# PSU.net
KiCad netlist of a schematic drawn in Altium Designer
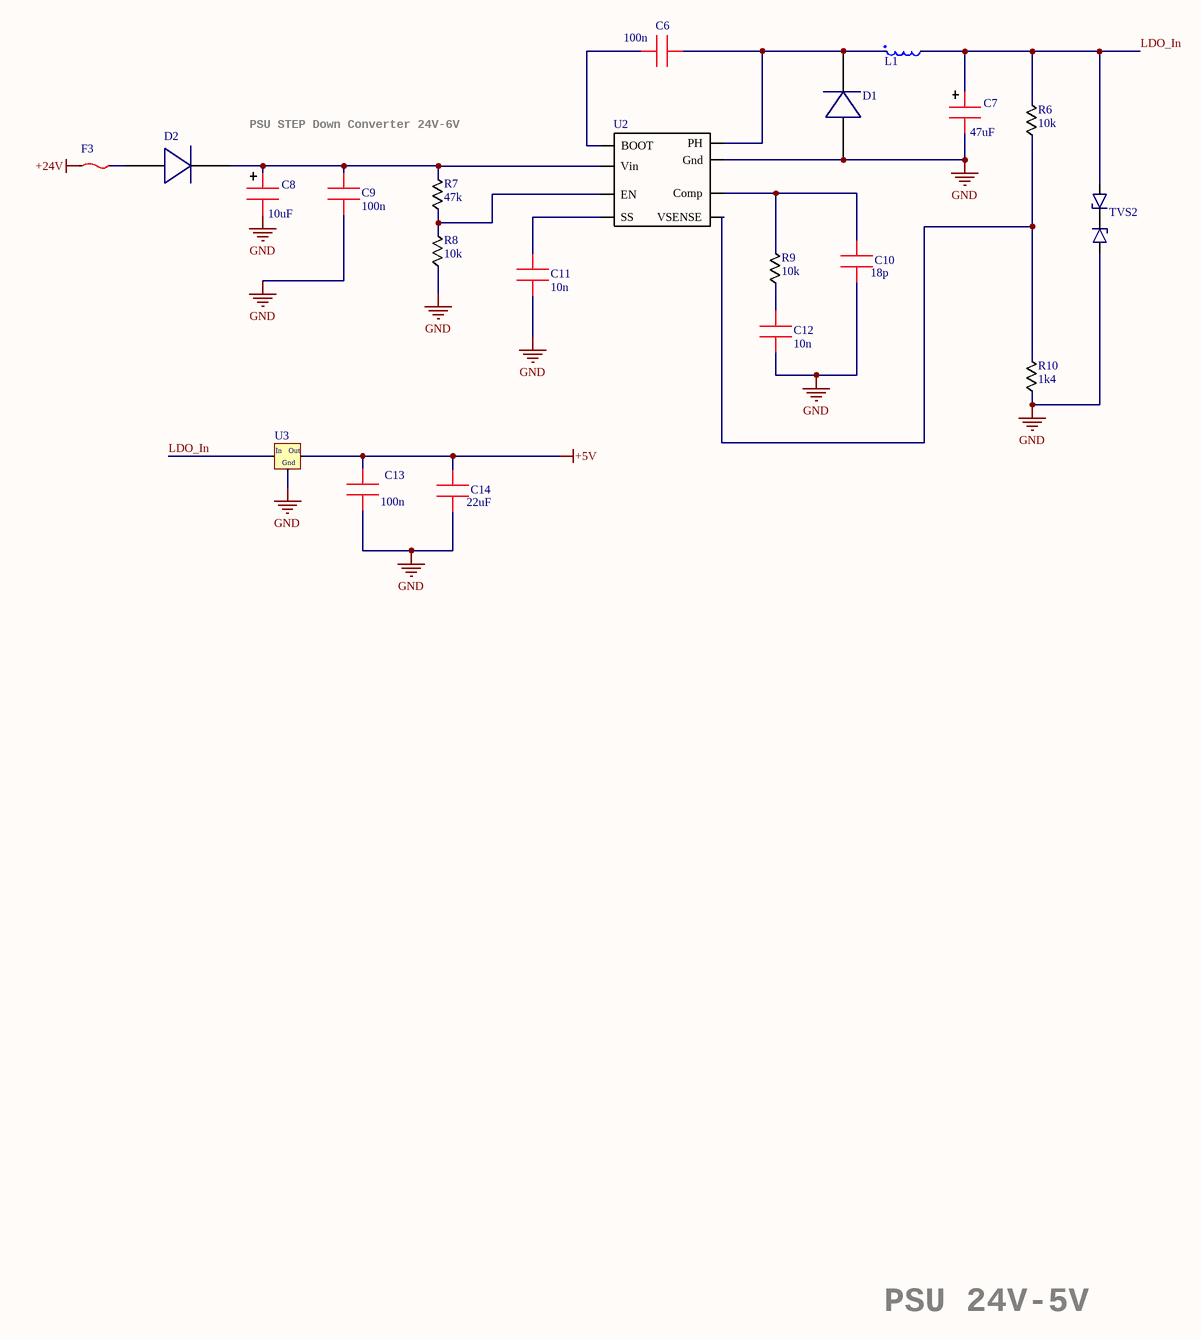
[diagram p0: PSU.SchDoc]

(export (version "E")
  (design (tool "Eeschema 10.0.6"))
  (components
    (comp (ref "C6")
      (value "100n")
      (footprint "0603 - Cap")
      (fields (field (name "PART NUMBER") "CC0603KRX7R9BB104"))
      (libsource (lib "kontr") (part "0805 Cap"))
    )
    (comp (ref "C7")
      (value "47uF")
      (footprint "1210")
      (fields (field (name "PART NUMBER") "GRM32ER71A476KE15L"))
      (libsource (lib "") (part "1206 Cap El_1"))
    )
    (comp (ref "C8")
      (value "10uF")
      (footprint "1210")
      (fields (field (name "PART NUMBER") "GRM32ER71H106KA12L"))
      (libsource (lib "kontr") (part "1206 Cap El"))
    )
    (comp (ref "C9")
      (value "100n")
      (footprint "0603 - Cap")
      (fields (field (name "PART NUMBER") "CC0603KRX7R9BB104"))
      (libsource (lib "kontr") (part "0805 Cap"))
    )
    (comp (ref "C10")
      (value "18p")
      (footprint "0603 - Cap")
      (fields (field (name "PART NUMBER") "CC0603JRNPO9BN180"))
      (libsource (lib "kontr") (part "0805 Cap"))
    )
    (comp (ref "C11")
      (value "10n")
      (footprint "0603 - Cap")
      (fields (field (name "PART NUMBER") "GRM1885C1H103JA01D"))
      (libsource (lib "kontr") (part "0805 Cap"))
    )
    (comp (ref "C12")
      (value "10n")
      (footprint "0603 - Cap")
      (fields (field (name "PART NUMBER") "GRM1885C1H103JA01D"))
      (libsource (lib "kontr") (part "0805 Cap"))
    )
    (comp (ref "C13")
      (value "100n")
      (footprint "0603 - Cap")
      (description "CC0603ZRY5V9BB104")
      (fields (field (name "PART NUMBER") "CC0603KRX7R9BB104"))
      (libsource (lib "kontr") (part "Capasitor 0805"))
    )
    (comp (ref "C14")
      (value "22uF")
      (footprint "1206")
      (fields (field (name "PART NUMBER") "CC1210KKX5R7BB226"))
      (libsource (lib "kontr") (part "0805 Cap"))
    )
    (comp (ref "D1")
      (value "~")
      (footprint "B340A-13-F")
      (fields (field (name "PART NUMBER") "B360A-13-F"))
      (libsource (lib "kontr") (part "B340A-13-F"))
    )
    (comp (ref "D2")
      (value "~")
      (footprint "B340A-13-F")
      (fields (field (name "PART NUMBER") "B360A-13-F"))
      (libsource (lib "kontr") (part "B340A-13-F"))
    )
    (comp (ref "F3")
      (value "~")
      (footprint "MSMF")
      (fields (field (name "PART NUMBER") "MF-MSMF010-2"))
      (libsource (lib "kontr") (part "MSMF"))
    )
    (comp (ref "L1")
      (value "~")
      (footprint "SRU1048")
      (fields (field (name "PART NUMBER") "SRU1048-330Y"))
      (libsource (lib "kontr") (part "CDRH127"))
    )
    (comp (ref "R6")
      (value "10k")
      (footprint "0603_Res")
      (fields (field (name "PART NUMBER") "RC0603FR-0710KL"))
      (libsource (lib "kontr") (part "Resistor 0805"))
    )
    (comp (ref "R7")
      (value "47k")
      (footprint "0603_Res")
      (description "RC0603JR-0747K")
      (libsource (lib "kontr") (part "Resistor 0805"))
    )
    (comp (ref "R8")
      (value "10k")
      (footprint "0603_Res")
      (fields (field (name "PART NUMBER") "RC0603FR-0710KL"))
      (libsource (lib "kontr") (part "Resistor 0805"))
    )
    (comp (ref "R9")
      (value "10k")
      (footprint "0603_Res")
      (fields (field (name "PART NUMBER") "RC0603FR-0710KL"))
      (libsource (lib "kontr") (part "Resistor 0805"))
    )
    (comp (ref "R10")
      (value "1k4")
      (footprint "0603_Res")
      (fields (field (name "PART NUMBER") "RC0603FR-071K4L"))
      (libsource (lib "kontr") (part "Resistor 0805"))
    )
    (comp (ref "TVS2")
      (value "~")
      (footprint "SM6T")
      (fields (field (name "PART NUMBER") "SM6T12CA"))
      (libsource (lib "kontr") (part "SM6T"))
    )
    (comp (ref "U2")
      (value "~")
      (footprint "SOIC 8")
      (fields (field (name "PART NUMBER") "TPS54331"))
      (libsource (lib "kontr") (part "TPS54331"))
    )
    (comp (ref "U3")
      (value "~")
      (footprint "SOT223")
      (fields (field (name "PART NUMBER") "LM1117MPX-5.0"))
      (libsource (lib "kontr") (part "NCV1117ST50T3G"))
    )
  )
  (nets
    (net (code "1") (name "+5V") (class "Default")
      (node (ref "C13") (pin "1") (pinfunction "1_1") (pintype "passive"))
      (node (ref "C14") (pin "2") (pinfunction "2_2") (pintype "passive"))
      (node (ref "U3") (pin "2") (pinfunction "OUT_2") (pintype "passive"))
    )
    (net (code "2") (name "+24V") (class "Default")
      (node (ref "F3") (pin "0") (pinfunction "0_0") (pintype "passive"))
    )
    (net (code "3") (name "/LDO_In") (class "Default")
      (node (ref "C7") (pin "1") (pinfunction "1_1") (pintype "passive"))
      (node (ref "L1") (pin "2") (pinfunction "2_2") (pintype "passive"))
      (node (ref "R6") (pin "2") (pintype "passive"))
      (node (ref "TVS2") (pin "2") (pinfunction "2_2") (pintype "passive"))
      (node (ref "U3") (pin "3") (pinfunction "IN_3") (pintype "passive"))
    )
    (net (code "4") (name "GND") (class "Default")
      (node (ref "C10") (pin "1") (pinfunction "1_1") (pintype "passive"))
      (node (ref "C11") (pin "1") (pinfunction "1_1") (pintype "passive"))
      (node (ref "C12") (pin "1") (pinfunction "1_1") (pintype "passive"))
      (node (ref "C13") (pin "2") (pinfunction "2_2") (pintype "passive"))
      (node (ref "C14") (pin "1") (pinfunction "1_1") (pintype "passive"))
      (node (ref "C7") (pin "2") (pinfunction "2_2") (pintype "passive"))
      (node (ref "C8") (pin "2") (pinfunction "2_2") (pintype "passive"))
      (node (ref "C9") (pin "1") (pinfunction "1_1") (pintype "passive"))
      (node (ref "D1") (pin "2") (pinfunction "1_2") (pintype "passive"))
      (node (ref "R10") (pin "1") (pintype "passive"))
      (node (ref "R8") (pin "1") (pintype "passive"))
      (node (ref "TVS2") (pin "1") (pinfunction "1_1") (pintype "passive"))
      (node (ref "U2") (pin "7") (pinfunction "Gnd_7") (pintype "passive"))
      (node (ref "U3") (pin "1") (pinfunction "GND_1") (pintype "passive"))
    )
    (net (code "5") (name "Net-(C12-Pad2)") (class "Default")
      (node (ref "C12") (pin "2") (pinfunction "2_2") (pintype "passive"))
      (node (ref "R9") (pin "1") (pintype "passive"))
    )
    (net (code "6") (name "Net-(D2-1-Pad2)") (class "Default")
      (node (ref "D2") (pin "2") (pinfunction "1_2") (pintype "passive"))
      (node (ref "F3") (pin "1") (pinfunction "1_1") (pintype "passive"))
    )
    (net (code "7") (name "Net-(U2-BOOT)") (class "Default")
      (node (ref "C6") (pin "1") (pinfunction "1_1") (pintype "passive"))
      (node (ref "U2") (pin "1") (pinfunction "BOOT_1") (pintype "passive"))
    )
    (net (code "8") (name "Net-(U2-Comp)") (class "Default")
      (node (ref "C10") (pin "2") (pinfunction "2_2") (pintype "passive"))
      (node (ref "R9") (pin "2") (pintype "passive"))
      (node (ref "U2") (pin "6") (pinfunction "Comp_6") (pintype "passive"))
    )
    (net (code "9") (name "Net-(U2-EN)") (class "Default")
      (node (ref "R7") (pin "1") (pintype "passive"))
      (node (ref "R8") (pin "2") (pintype "passive"))
      (node (ref "U2") (pin "3") (pinfunction "EN_3") (pintype "passive"))
    )
    (net (code "10") (name "Net-(U2-PH)") (class "Default")
      (node (ref "C6") (pin "2") (pinfunction "2_2") (pintype "passive"))
      (node (ref "D1") (pin "1") (pinfunction "1_1") (pintype "passive"))
      (node (ref "L1") (pin "1") (pinfunction "1_1") (pintype "passive"))
      (node (ref "U2") (pin "8") (pinfunction "PH_8") (pintype "passive"))
    )
    (net (code "11") (name "Net-(U2-SS)") (class "Default")
      (node (ref "C11") (pin "2") (pinfunction "2_2") (pintype "passive"))
      (node (ref "U2") (pin "4") (pinfunction "SS_4") (pintype "passive"))
    )
    (net (code "12") (name "Net-(U2-VSENSE)") (class "Default")
      (node (ref "R10") (pin "2") (pintype "passive"))
      (node (ref "R6") (pin "1") (pintype "passive"))
      (node (ref "U2") (pin "5") (pinfunction "VSENSE_5") (pintype "passive"))
    )
    (net (code "13") (name "Net-(U2-Vin)") (class "Default")
      (node (ref "C8") (pin "1") (pinfunction "1_1") (pintype "passive"))
      (node (ref "C9") (pin "2") (pinfunction "2_2") (pintype "passive"))
      (node (ref "D2") (pin "1") (pinfunction "1_1") (pintype "passive"))
      (node (ref "R7") (pin "2") (pintype "passive"))
      (node (ref "U2") (pin "2") (pinfunction "Vin_2") (pintype "passive"))
    )
  )
)
